# ver2_0.net
KiCad netlist of a schematic drawn in EAGLE
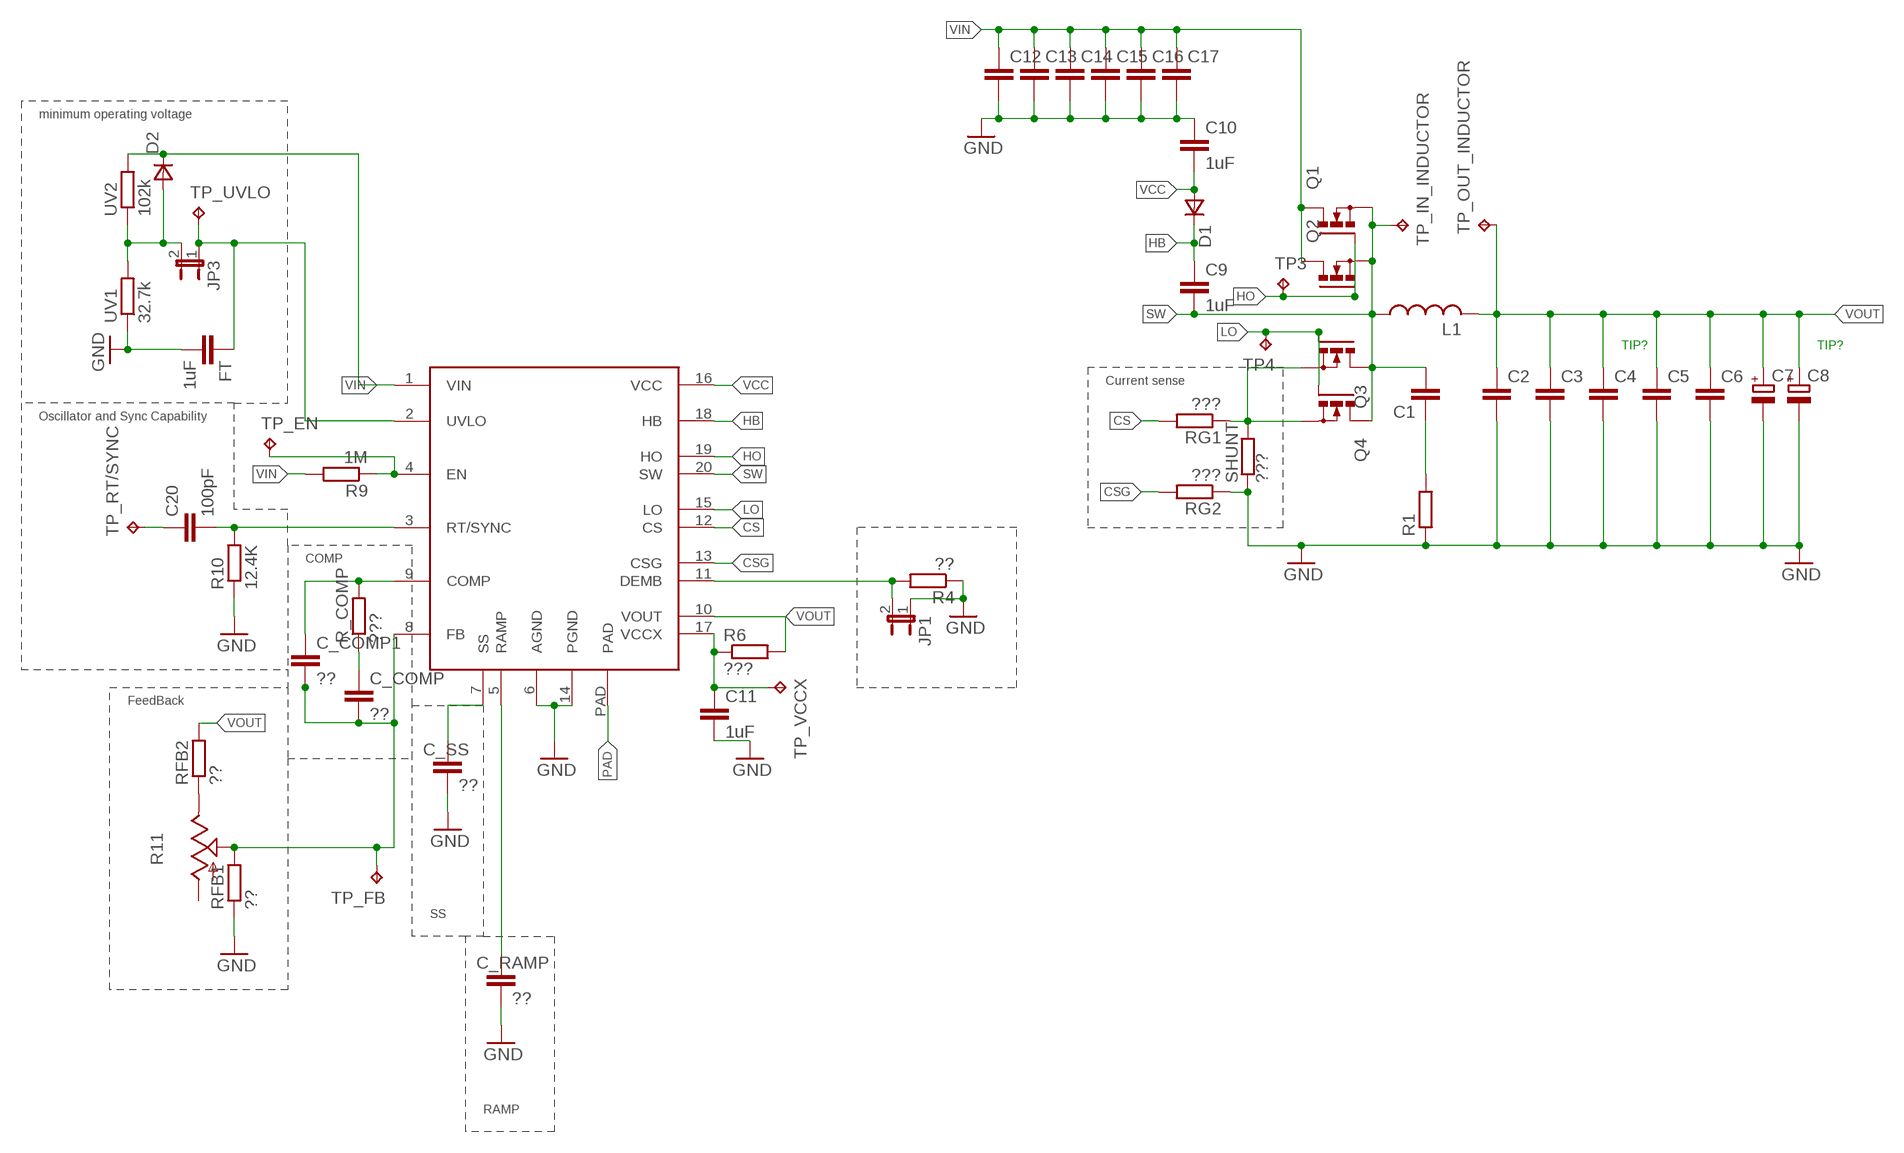
[diagram p0: schematic, sheet 1]

(export (version "E")
  (design (tool "Eeschema 10.0.6"))
  (components
    (comp (ref "C1")
      (value "C-EUC0805K")
      (footprint "eagle-import:C0805K")
      (libsource (lib "eagle-import") (part "resistor_C-EUC0805K"))
    )
    (comp (ref "C2")
      (value "C-EUC1812")
      (footprint "eagle-import:C1812")
      (libsource (lib "eagle-import") (part "C-EUC1812"))
    )
    (comp (ref "C3")
      (value "C-EUC1812")
      (footprint "eagle-import:C1812")
      (libsource (lib "eagle-import") (part "C-EUC1812"))
    )
    (comp (ref "C4")
      (value "C-EUC1812")
      (footprint "eagle-import:C1812")
      (libsource (lib "eagle-import") (part "C-EUC1812"))
    )
    (comp (ref "C5")
      (value "C-EUC1812")
      (footprint "eagle-import:C1812")
      (libsource (lib "eagle-import") (part "C-EUC1812"))
    )
    (comp (ref "C6")
      (value "C-EUC1812")
      (footprint "eagle-import:C1812")
      (libsource (lib "eagle-import") (part "C-EUC1812"))
    )
    (comp (ref "C7")
      (value "CPOL-EU153CLV-1012")
      (footprint "eagle-import:153CLV-1012")
      (libsource (lib "eagle-import") (part "CPOL-EU153CLV-1012"))
    )
    (comp (ref "C8")
      (value "CPOL-EU153CLV-1012")
      (footprint "eagle-import:153CLV-1012")
      (libsource (lib "eagle-import") (part "CPOL-EU153CLV-1012"))
    )
    (comp (ref "C9")
      (value "1uF")
      (footprint "eagle-import:C0805K")
      (libsource (lib "eagle-import") (part "resistor_C-EUC0805K"))
    )
    (comp (ref "C10")
      (value "1uF")
      (footprint "eagle-import:C0805K")
      (libsource (lib "eagle-import") (part "resistor_C-EUC0805K"))
    )
    (comp (ref "C11")
      (value "1uF")
      (footprint "eagle-import:C0805K")
      (libsource (lib "eagle-import") (part "resistor_C-EUC0805K"))
    )
    (comp (ref "C12")
      (value "C-EUC1812K")
      (footprint "eagle-import:C1812K")
      (libsource (lib "eagle-import") (part "C-EUC1812K"))
    )
    (comp (ref "C13")
      (value "C-EUC1812K")
      (footprint "eagle-import:C1812K")
      (libsource (lib "eagle-import") (part "C-EUC1812K"))
    )
    (comp (ref "C14")
      (value "C-EUC1812K")
      (footprint "eagle-import:C1812K")
      (libsource (lib "eagle-import") (part "C-EUC1812K"))
    )
    (comp (ref "C15")
      (value "C-EUC1812K")
      (footprint "eagle-import:C1812K")
      (libsource (lib "eagle-import") (part "C-EUC1812K"))
    )
    (comp (ref "C16")
      (value "C-EUC1812K")
      (footprint "eagle-import:C1812K")
      (libsource (lib "eagle-import") (part "C-EUC1812K"))
    )
    (comp (ref "C17")
      (value "C-EUC1812K")
      (footprint "eagle-import:C1812K")
      (libsource (lib "eagle-import") (part "C-EUC1812K"))
    )
    (comp (ref "C20")
      (value "100pF")
      (footprint "eagle-import:C0805K")
      (libsource (lib "eagle-import") (part "resistor_C-EUC0805K"))
    )
    (comp (ref "C_COMP")
      (value "??")
      (footprint "eagle-import:C0805K")
      (libsource (lib "eagle-import") (part "resistor_C-EUC0805K"))
    )
    (comp (ref "C_COMP1")
      (value "??")
      (footprint "eagle-import:C0805K")
      (libsource (lib "eagle-import") (part "resistor_C-EUC0805K"))
    )
    (comp (ref "C_RAMP")
      (value "??")
      (footprint "eagle-import:C0805K")
      (libsource (lib "eagle-import") (part "resistor_C-EUC0805K"))
    )
    (comp (ref "C_SS")
      (value "??")
      (footprint "eagle-import:C0805K")
      (libsource (lib "eagle-import") (part "resistor_C-EUC0805K"))
    )
    (comp (ref "D1")
      (value "DSOT23")
      (footprint "eagle-import:SOT-23")
      (fields (field (name "MPN") "CDSOT23-T03"))
      (libsource (lib "eagle-import") (part "DSOT23"))
    )
    (comp (ref "D2")
      (value "DSOT23")
      (footprint "eagle-import:SOT-23")
      (fields (field (name "MPN") "CDSOT23-T03"))
      (libsource (lib "eagle-import") (part "DSOT23"))
    )
    (comp (ref "FT")
      (value "1uF")
      (footprint "eagle-import:C1812K")
      (libsource (lib "eagle-import") (part "C-EUC1812K"))
    )
    (comp (ref "JP1")
      (value "JP1E")
      (footprint "eagle-import:JP1")
      (libsource (lib "eagle-import") (part "JP1E"))
    )
    (comp (ref "JP3")
      (value "JP1E")
      (footprint "eagle-import:JP1")
      (libsource (lib "eagle-import") (part "JP1E"))
    )
    (comp (ref "L1")
      (value "L-USTJ8-U2")
      (footprint "eagle-import:TJ8-U2")
      (libsource (lib "eagle-import") (part "L-USTJ8-U2"))
    )
    (comp (ref "Q1")
      (value "PMOSFET_NTO220BH")
      (footprint "eagle-import:TO220BH")
      (libsource (lib "eagle-import") (part "PMOSFET_NTO220BH"))
    )
    (comp (ref "Q2")
      (value "PMOSFET_NTO220BH")
      (footprint "eagle-import:TO220BH")
      (libsource (lib "eagle-import") (part "PMOSFET_NTO220BH"))
    )
    (comp (ref "Q3")
      (value "PMOSFET_NTO220BH")
      (footprint "eagle-import:TO220BH")
      (libsource (lib "eagle-import") (part "PMOSFET_NTO220BH"))
    )
    (comp (ref "Q4")
      (value "PMOSFET_NTO220BH")
      (footprint "eagle-import:TO220BH")
      (libsource (lib "eagle-import") (part "PMOSFET_NTO220BH"))
    )
    (comp (ref "R1")
      (value "R-EU_M1206")
      (footprint "eagle-import:M1206")
      (libsource (lib "eagle-import") (part "resistor_R-EU_M1206"))
    )
    (comp (ref "R4")
      (value "??")
      (footprint "eagle-import:R0603")
      (libsource (lib "eagle-import") (part "R-EU_R0603"))
    )
    (comp (ref "R6")
      (value "???")
      (footprint "eagle-import:R0603")
      (libsource (lib "eagle-import") (part "R-EU_R0603"))
    )
    (comp (ref "R9")
      (value "1M")
      (footprint "eagle-import:R0603")
      (libsource (lib "eagle-import") (part "R-EU_R0603"))
    )
    (comp (ref "R10")
      (value "12.4K")
      (footprint "eagle-import:R0603")
      (libsource (lib "eagle-import") (part "R-EU_R0603"))
    )
    (comp (ref "R11")
      (value "TRIM_US-B64Y")
      (footprint "eagle-import:B64Y")
      (libsource (lib "eagle-import") (part "TRIM_US-B64Y"))
    )
    (comp (ref "RFB1")
      (value "??")
      (footprint "eagle-import:R0603")
      (libsource (lib "eagle-import") (part "R-EU_R0603"))
    )
    (comp (ref "RFB2")
      (value "??")
      (footprint "eagle-import:R0603")
      (libsource (lib "eagle-import") (part "R-EU_R0603"))
    )
    (comp (ref "RG1")
      (value "???")
      (footprint "eagle-import:R0603")
      (libsource (lib "eagle-import") (part "R-EU_R0603"))
    )
    (comp (ref "RG2")
      (value "???")
      (footprint "eagle-import:R0603")
      (libsource (lib "eagle-import") (part "R-EU_R0603"))
    )
    (comp (ref "R_COMP")
      (value "???")
      (footprint "eagle-import:R0603")
      (libsource (lib "eagle-import") (part "R-EU_R0603"))
    )
    (comp (ref "SHUNT")
      (value "???")
      (footprint "eagle-import:SMR-0")
      (libsource (lib "eagle-import") (part "SMR-0"))
    )
    (comp (ref "TP3")
      (value "TPPAD1-20")
      (footprint "eagle-import:P1-20")
      (libsource (lib "eagle-import") (part "TPPAD1-20"))
    )
    (comp (ref "TP4")
      (value "TPPAD1-20")
      (footprint "eagle-import:P1-20")
      (libsource (lib "eagle-import") (part "TPPAD1-20"))
    )
    (comp (ref "TP_EN")
      (value "TPPAD1-20")
      (footprint "eagle-import:P1-20")
      (libsource (lib "eagle-import") (part "TPPAD1-20"))
    )
    (comp (ref "TP_FB")
      (value "TPPAD1-20")
      (footprint "eagle-import:P1-20")
      (libsource (lib "eagle-import") (part "TPPAD1-20"))
    )
    (comp (ref "TP_IN_INDUCTOR")
      (value "TPPAD1-20")
      (footprint "eagle-import:P1-20")
      (libsource (lib "eagle-import") (part "TPPAD1-20"))
    )
    (comp (ref "TP_OUT_INDUCTOR")
      (value "TPPAD1-20")
      (footprint "eagle-import:P1-20")
      (libsource (lib "eagle-import") (part "TPPAD1-20"))
    )
    (comp (ref "TP_RT/SYNC")
      (value "TPPAD1-20")
      (footprint "eagle-import:P1-20")
      (libsource (lib "eagle-import") (part "TPPAD1-20"))
    )
    (comp (ref "TP_UVLO")
      (value "TPPAD1-20")
      (footprint "eagle-import:P1-20")
      (libsource (lib "eagle-import") (part "TPPAD1-20"))
    )
    (comp (ref "TP_VCCX")
      (value "TPPAD1-20")
      (footprint "eagle-import:P1-20")
      (libsource (lib "eagle-import") (part "TPPAD1-20"))
    )
    (comp (ref "U$1")
      (value "LM5116")
      (footprint "eagle-import:TSSOP20")
      (libsource (lib "eagle-import") (part "LM5116"))
    )
    (comp (ref "UV1")
      (value "32.7k")
      (footprint "eagle-import:R0603")
      (libsource (lib "eagle-import") (part "R-EU_R0603"))
    )
    (comp (ref "UV2")
      (value "102k")
      (footprint "eagle-import:R0603")
      (libsource (lib "eagle-import") (part "R-EU_R0603"))
    )
  )
  (nets
    (net (code "1") (name "CS") (class "Default")
      (node (ref "RG1") (pin "2") (pinfunction "2_2") (pintype "passive"))
      (node (ref "U$1") (pin "12") (pinfunction "CS_12") (pintype "bidirectional"))
    )
    (net (code "2") (name "CSG") (class "Default")
      (node (ref "RG2") (pin "2") (pinfunction "2_2") (pintype "passive"))
      (node (ref "U$1") (pin "13") (pinfunction "CSG_13") (pintype "bidirectional"))
    )
    (net (code "3") (name "GND") (class "Default")
      (node (ref "C10") (pin "1") (pinfunction "1_1") (pintype "passive"))
      (node (ref "C11") (pin "2") (pinfunction "2_2") (pintype "passive"))
      (node (ref "C12") (pin "2") (pinfunction "2_2") (pintype "passive"))
      (node (ref "C13") (pin "2") (pinfunction "2_2") (pintype "passive"))
      (node (ref "C14") (pin "2") (pinfunction "2_2") (pintype "passive"))
      (node (ref "C15") (pin "2") (pinfunction "2_2") (pintype "passive"))
      (node (ref "C16") (pin "2") (pinfunction "2_2") (pintype "passive"))
      (node (ref "C17") (pin "2") (pinfunction "2_2") (pintype "passive"))
      (node (ref "C2") (pin "2") (pinfunction "2_2") (pintype "passive"))
      (node (ref "C3") (pin "2") (pinfunction "2_2") (pintype "passive"))
      (node (ref "C4") (pin "2") (pinfunction "2_2") (pintype "passive"))
      (node (ref "C5") (pin "2") (pinfunction "2_2") (pintype "passive"))
      (node (ref "C6") (pin "2") (pinfunction "2_2") (pintype "passive"))
      (node (ref "C7") (pin "-") (pinfunction "-_-") (pintype "passive"))
      (node (ref "C8") (pin "-") (pinfunction "-_-") (pintype "passive"))
      (node (ref "C_RAMP") (pin "2") (pinfunction "2_2") (pintype "passive"))
      (node (ref "C_SS") (pin "2") (pinfunction "2_2") (pintype "passive"))
      (node (ref "FT") (pin "2") (pinfunction "2_2") (pintype "passive"))
      (node (ref "JP1") (pin "1") (pinfunction "1_1") (pintype "passive"))
      (node (ref "R1") (pin "1") (pinfunction "1_1") (pintype "passive"))
      (node (ref "R10") (pin "1") (pinfunction "1_1") (pintype "passive"))
      (node (ref "R4") (pin "1") (pinfunction "1_1") (pintype "passive"))
      (node (ref "RFB1") (pin "1") (pinfunction "1_1") (pintype "passive"))
      (node (ref "RG2") (pin "1") (pinfunction "1_1") (pintype "passive"))
      (node (ref "SHUNT") (pin "2") (pinfunction "2_2") (pintype "passive"))
      (node (ref "U$1") (pin "14") (pinfunction "PGND_14") (pintype "bidirectional"))
      (node (ref "U$1") (pin "6") (pinfunction "AGND_6") (pintype "bidirectional"))
      (node (ref "UV1") (pin "1") (pinfunction "1_1") (pintype "passive"))
    )
    (net (code "4") (name "HB") (class "Default")
      (node (ref "C9") (pin "1") (pinfunction "1_1") (pintype "passive"))
      (node (ref "D1") (pin "1") (pinfunction "C_1") (pintype "passive"))
      (node (ref "U$1") (pin "18") (pinfunction "HB_18") (pintype "bidirectional"))
    )
    (net (code "5") (name "HO") (class "Default")
      (node (ref "Q1") (pin "G") (pinfunction "G_G") (pintype "passive"))
      (node (ref "Q2") (pin "G") (pinfunction "G_G") (pintype "passive"))
      (node (ref "TP3") (pin "TP") (pinfunction "TP_TP") (pintype "input"))
      (node (ref "U$1") (pin "19") (pinfunction "HO_19") (pintype "bidirectional"))
    )
    (net (code "6") (name "LO") (class "Default")
      (node (ref "Q3") (pin "G") (pinfunction "G_G") (pintype "passive"))
      (node (ref "Q4") (pin "G") (pinfunction "G_G") (pintype "passive"))
      (node (ref "TP4") (pin "TP") (pinfunction "TP_TP") (pintype "input"))
      (node (ref "U$1") (pin "15") (pinfunction "LO_15") (pintype "bidirectional"))
    )
    (net (code "7") (name "Net-(C1-Pad1)") (class "Default")
      (node (ref "C1") (pin "1") (pinfunction "1_1") (pintype "passive"))
      (node (ref "R1") (pin "2") (pinfunction "2_2") (pintype "passive"))
    )
    (net (code "8") (name "Net-(C20-Pad1)") (class "Default")
      (node (ref "C20") (pin "1") (pinfunction "1_1") (pintype "passive"))
      (node (ref "TP_RT/SYNC") (pin "TP") (pinfunction "TP_TP") (pintype "input"))
    )
    (net (code "9") (name "Net-(C_COMP-Pad1)") (class "Default")
      (node (ref "C_COMP") (pin "1") (pinfunction "1_1") (pintype "passive"))
      (node (ref "R_COMP") (pin "1") (pinfunction "1_1") (pintype "passive"))
    )
    (net (code "10") (name "Net-(D2-A)") (class "Default")
      (node (ref "D2") (pin "3") (pinfunction "A_3") (pintype "passive"))
      (node (ref "JP3") (pin "2") (pinfunction "2_2") (pintype "passive"))
      (node (ref "UV1") (pin "2") (pinfunction "2_2") (pintype "passive"))
      (node (ref "UV2") (pin "1") (pinfunction "1_1") (pintype "passive"))
    )
    (net (code "11") (name "Net-(Q3-PadS)") (class "Default")
      (node (ref "Q3") (pin "S") (pinfunction "S_S") (pintype "passive"))
      (node (ref "Q4") (pin "S") (pinfunction "S_S") (pintype "passive"))
      (node (ref "RG1") (pin "1") (pinfunction "1_1") (pintype "passive"))
      (node (ref "SHUNT") (pin "1") (pinfunction "1_1") (pintype "passive"))
    )
    (net (code "12") (name "Net-(R11-PadE)") (class "Default")
      (node (ref "R11") (pin "E") (pinfunction "E_E") (pintype "passive"))
      (node (ref "RFB2") (pin "1") (pinfunction "1_1") (pintype "passive"))
    )
    (net (code "13") (name "Net-(U$1-COMP)") (class "Default")
      (node (ref "C_COMP1") (pin "1") (pinfunction "1_1") (pintype "passive"))
      (node (ref "R_COMP") (pin "2") (pinfunction "2_2") (pintype "passive"))
      (node (ref "U$1") (pin "9") (pinfunction "COMP_9") (pintype "bidirectional"))
    )
    (net (code "14") (name "Net-(U$1-DEMB)") (class "Default")
      (node (ref "JP1") (pin "2") (pinfunction "2_2") (pintype "passive"))
      (node (ref "R4") (pin "2") (pinfunction "2_2") (pintype "passive"))
      (node (ref "U$1") (pin "11") (pinfunction "DEMB_11") (pintype "bidirectional"))
    )
    (net (code "15") (name "Net-(U$1-EN)") (class "Default")
      (node (ref "R9") (pin "1") (pinfunction "1_1") (pintype "passive"))
      (node (ref "TP_EN") (pin "TP") (pinfunction "TP_TP") (pintype "input"))
      (node (ref "U$1") (pin "4") (pinfunction "EN_4") (pintype "bidirectional"))
    )
    (net (code "16") (name "Net-(U$1-FB)") (class "Default")
      (node (ref "C_COMP") (pin "2") (pinfunction "2_2") (pintype "passive"))
      (node (ref "C_COMP1") (pin "2") (pinfunction "2_2") (pintype "passive"))
      (node (ref "R11") (pin "S") (pinfunction "S_S") (pintype "passive"))
      (node (ref "RFB1") (pin "2") (pinfunction "2_2") (pintype "passive"))
      (node (ref "TP_FB") (pin "TP") (pinfunction "TP_TP") (pintype "input"))
      (node (ref "U$1") (pin "8") (pinfunction "FB_8") (pintype "bidirectional"))
    )
    (net (code "17") (name "Net-(U$1-RAMP)") (class "Default")
      (node (ref "C_RAMP") (pin "1") (pinfunction "1_1") (pintype "passive"))
      (node (ref "U$1") (pin "5") (pinfunction "RAMP_5") (pintype "bidirectional"))
    )
    (net (code "18") (name "Net-(U$1-RT{slash}SYNC)") (class "Default")
      (node (ref "C20") (pin "2") (pinfunction "2_2") (pintype "passive"))
      (node (ref "R10") (pin "2") (pinfunction "2_2") (pintype "passive"))
      (node (ref "U$1") (pin "3") (pinfunction "RT/SYNC_3") (pintype "bidirectional"))
    )
    (net (code "19") (name "Net-(U$1-SS)") (class "Default")
      (node (ref "C_SS") (pin "1") (pinfunction "1_1") (pintype "passive"))
      (node (ref "U$1") (pin "7") (pinfunction "SS_7") (pintype "bidirectional"))
    )
    (net (code "20") (name "Net-(U$1-UVLO)") (class "Default")
      (node (ref "FT") (pin "1") (pinfunction "1_1") (pintype "passive"))
      (node (ref "JP3") (pin "1") (pinfunction "1_1") (pintype "passive"))
      (node (ref "TP_UVLO") (pin "TP") (pinfunction "TP_TP") (pintype "input"))
      (node (ref "U$1") (pin "2") (pinfunction "UVLO_2") (pintype "bidirectional"))
    )
    (net (code "21") (name "Net-(U$1-VCCX)") (class "Default")
      (node (ref "C11") (pin "1") (pinfunction "1_1") (pintype "passive"))
      (node (ref "R6") (pin "1") (pinfunction "1_1") (pintype "passive"))
      (node (ref "TP_VCCX") (pin "TP") (pinfunction "TP_TP") (pintype "input"))
      (node (ref "U$1") (pin "17") (pinfunction "VCCX_17") (pintype "bidirectional"))
    )
    (net (code "22") (name "PAD") (class "Default")
      (node (ref "U$1") (pin "PAD") (pinfunction "PAD_PAD") (pintype "bidirectional"))
    )
    (net (code "23") (name "SW") (class "Default")
      (node (ref "C1") (pin "2") (pinfunction "2_2") (pintype "passive"))
      (node (ref "C9") (pin "2") (pinfunction "2_2") (pintype "passive"))
      (node (ref "L1") (pin "1") (pinfunction "1_1") (pintype "passive"))
      (node (ref "Q1") (pin "S") (pinfunction "S_S") (pintype "passive"))
      (node (ref "Q2") (pin "S") (pinfunction "S_S") (pintype "passive"))
      (node (ref "Q3") (pin "D") (pinfunction "D_D") (pintype "passive"))
      (node (ref "Q4") (pin "D") (pinfunction "D_D") (pintype "passive"))
      (node (ref "TP_IN_INDUCTOR") (pin "TP") (pinfunction "TP_TP") (pintype "input"))
      (node (ref "U$1") (pin "20") (pinfunction "SW_20") (pintype "bidirectional"))
    )
    (net (code "24") (name "VCC") (class "Default")
      (node (ref "C10") (pin "2") (pinfunction "2_2") (pintype "passive"))
      (node (ref "D1") (pin "3") (pinfunction "A_3") (pintype "passive"))
      (node (ref "U$1") (pin "16") (pinfunction "VCC_16") (pintype "bidirectional"))
    )
    (net (code "25") (name "VIN") (class "Default")
      (node (ref "C12") (pin "1") (pinfunction "1_1") (pintype "passive"))
      (node (ref "C13") (pin "1") (pinfunction "1_1") (pintype "passive"))
      (node (ref "C14") (pin "1") (pinfunction "1_1") (pintype "passive"))
      (node (ref "C15") (pin "1") (pinfunction "1_1") (pintype "passive"))
      (node (ref "C16") (pin "1") (pinfunction "1_1") (pintype "passive"))
      (node (ref "C17") (pin "1") (pinfunction "1_1") (pintype "passive"))
      (node (ref "D2") (pin "1") (pinfunction "C_1") (pintype "passive"))
      (node (ref "Q1") (pin "D") (pinfunction "D_D") (pintype "passive"))
      (node (ref "Q2") (pin "D") (pinfunction "D_D") (pintype "passive"))
      (node (ref "R9") (pin "2") (pinfunction "2_2") (pintype "passive"))
      (node (ref "U$1") (pin "1") (pinfunction "VIN_1") (pintype "power_in"))
      (node (ref "UV2") (pin "2") (pinfunction "2_2") (pintype "passive"))
    )
    (net (code "26") (name "VOUT") (class "Default")
      (node (ref "C2") (pin "1") (pinfunction "1_1") (pintype "passive"))
      (node (ref "C3") (pin "1") (pinfunction "1_1") (pintype "passive"))
      (node (ref "C4") (pin "1") (pinfunction "1_1") (pintype "passive"))
      (node (ref "C5") (pin "1") (pinfunction "1_1") (pintype "passive"))
      (node (ref "C6") (pin "1") (pinfunction "1_1") (pintype "passive"))
      (node (ref "C7") (pin "+") (pinfunction "+_+") (pintype "passive"))
      (node (ref "C8") (pin "+") (pinfunction "+_+") (pintype "passive"))
      (node (ref "L1") (pin "2") (pinfunction "2_2") (pintype "passive"))
      (node (ref "R6") (pin "2") (pinfunction "2_2") (pintype "passive"))
      (node (ref "RFB2") (pin "2") (pinfunction "2_2") (pintype "passive"))
      (node (ref "TP_OUT_INDUCTOR") (pin "TP") (pinfunction "TP_TP") (pintype "input"))
      (node (ref "U$1") (pin "10") (pinfunction "VOUT_10") (pintype "bidirectional"))
    )
    (net (code "27") (name "unconnected-(R11-PadA)") (class "Default")
      (node (ref "R11") (pin "A") (pinfunction "A_A") (pintype "passive"))
    )
  )
)
